# eSAS_BNC_fanout.net
KiCad netlist of a schematic drawn in Altium Designer
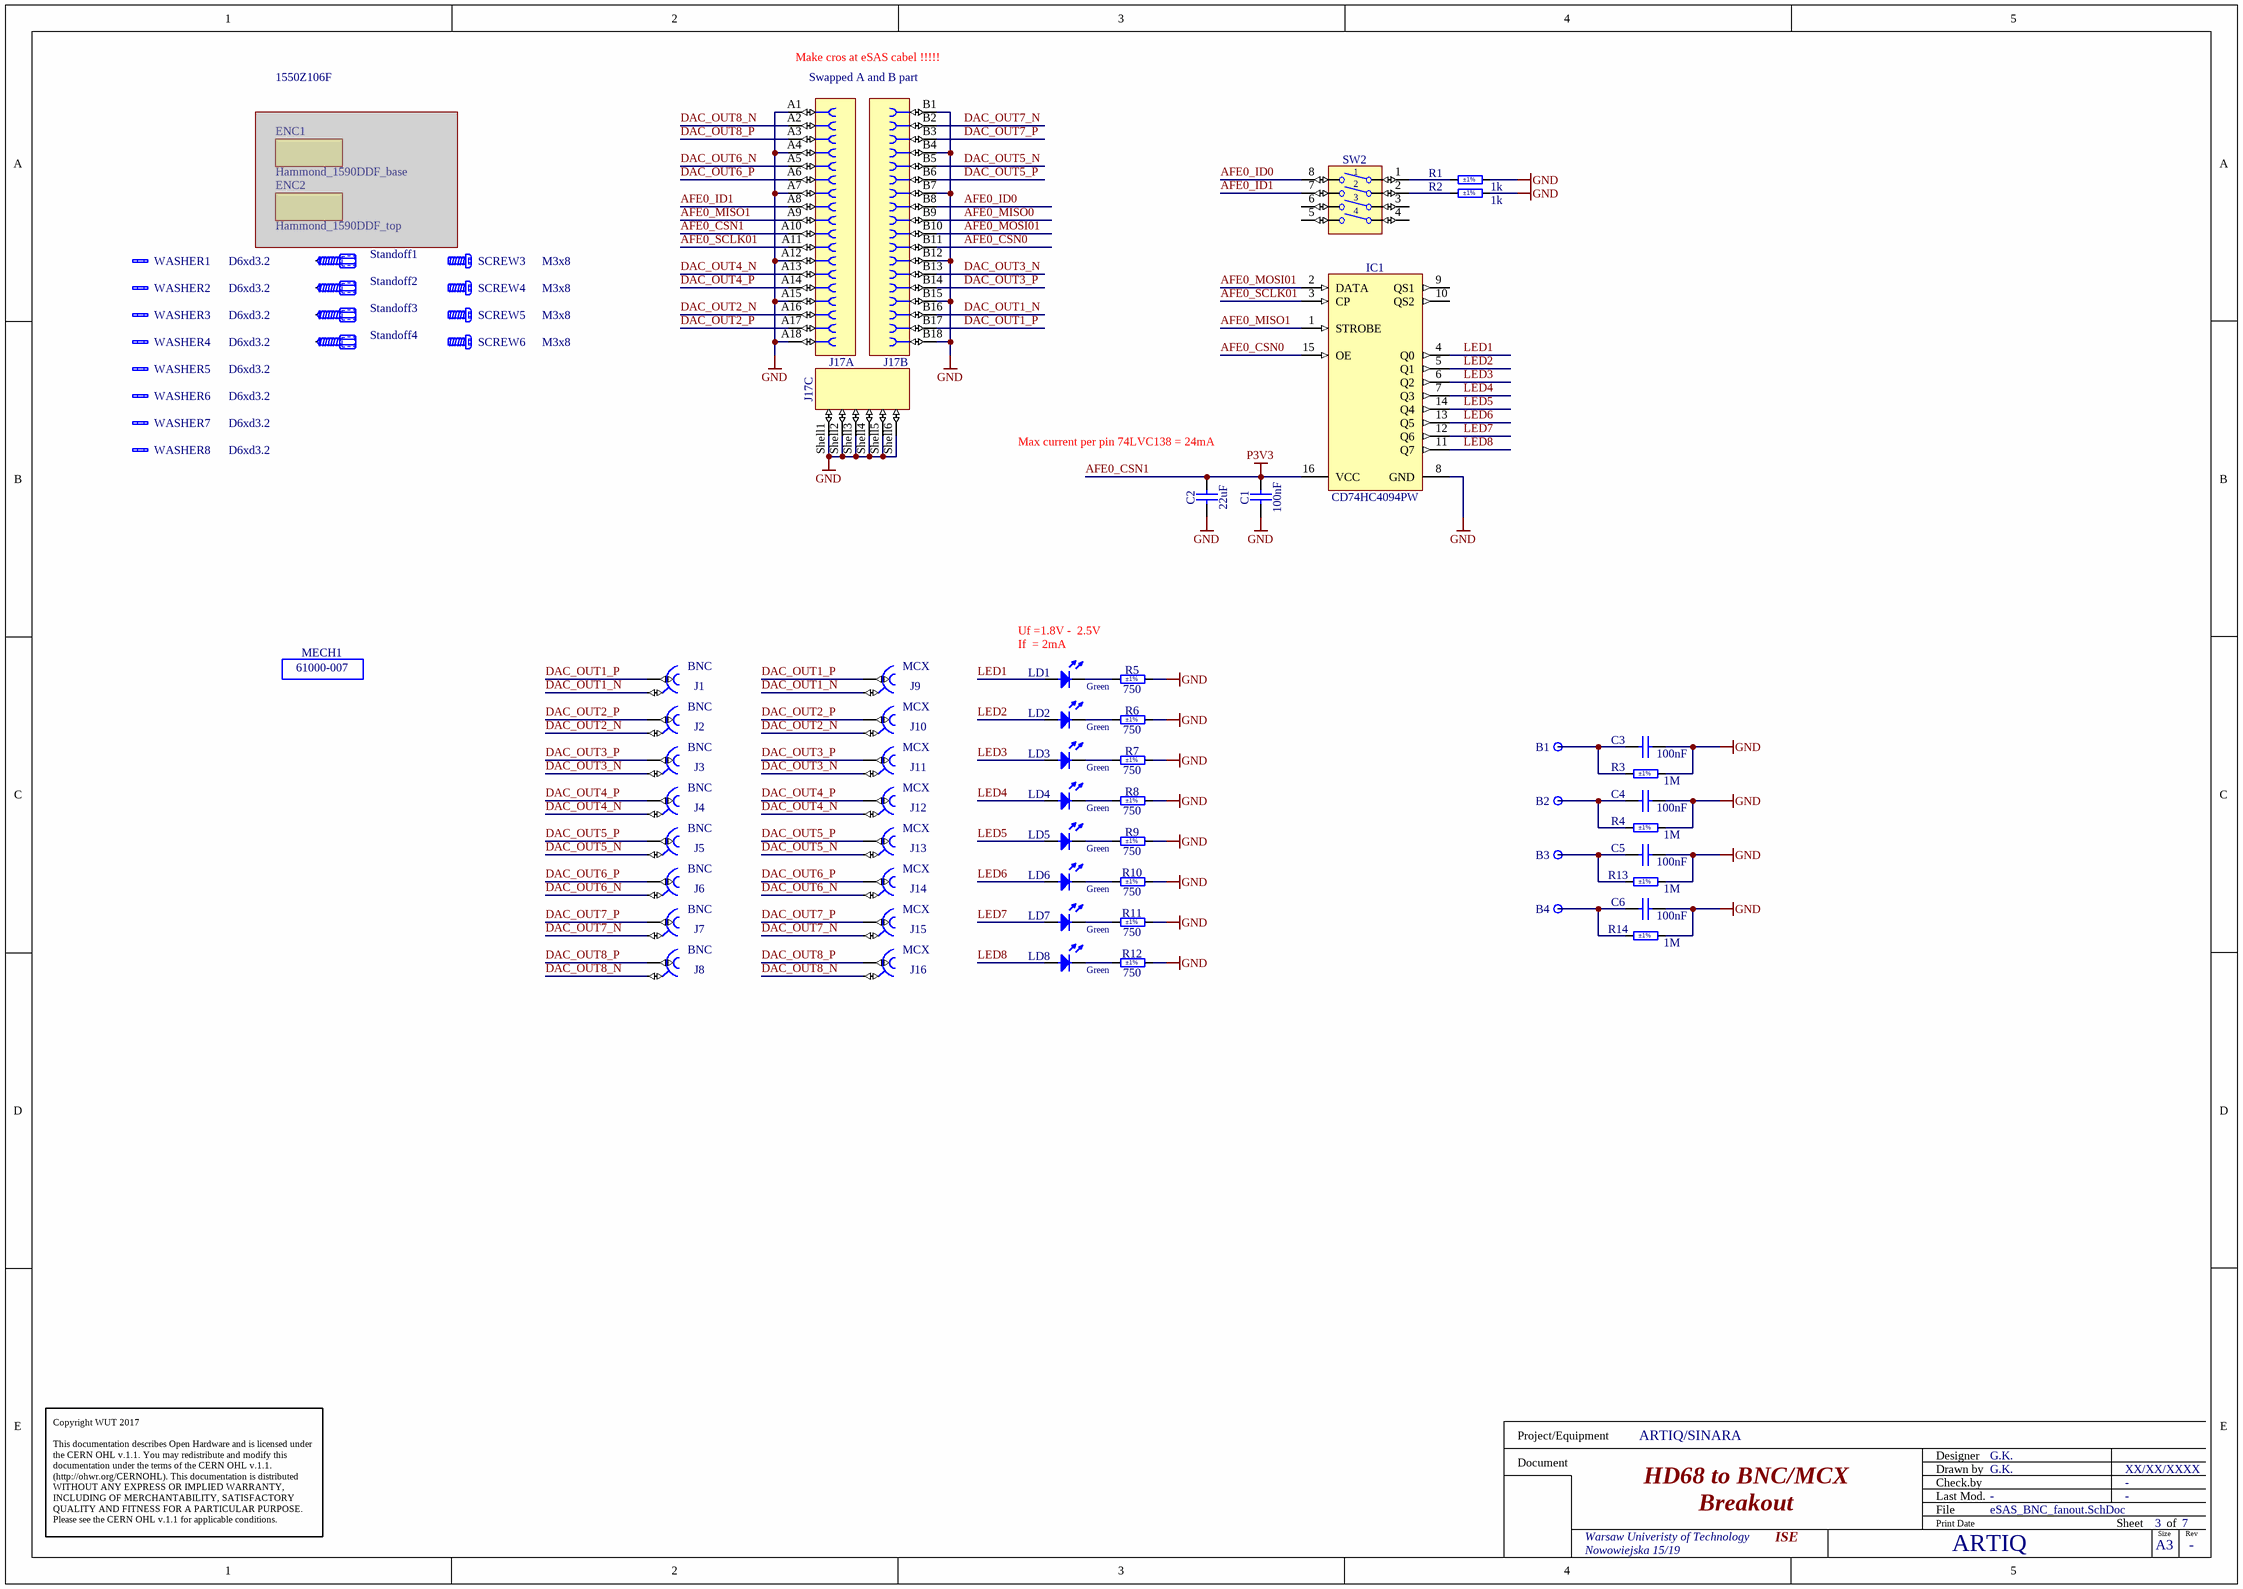
[diagram p0: eSAS_BNC_fanout.SchDoc]

(export (version "E")
  (design (tool "Eeschema 10.0.6"))
  (components
    (comp (ref "B1")
      (value "Plated Hole")
      (footprint "MTG270_500")
      (description "Single Terminal Socket")
      (fields (field (name "PART NUMBER") "PLATED_HOLE2.7_PAD5.0") (field (name "AUTHOR") "CERN DEM JMW"))
      (libsource (lib "Eletro-mechanical") (part "Single Terminal Socket"))
    )
    (comp (ref "B2")
      (value "Plated Hole")
      (footprint "MTG270_500")
      (description "Single Terminal Socket")
      (fields (field (name "PART NUMBER") "PLATED_HOLE2.7_PAD5.0") (field (name "AUTHOR") "CERN DEM JMW"))
      (libsource (lib "Eletro-mechanical") (part "Single Terminal Socket"))
    )
    (comp (ref "B3")
      (value "Plated Hole")
      (footprint "MTG270_500")
      (description "Single Terminal Socket")
      (fields (field (name "PART NUMBER") "PLATED_HOLE2.7_PAD5.0") (field (name "AUTHOR") "CERN DEM JMW"))
      (libsource (lib "Eletro-mechanical") (part "Single Terminal Socket"))
    )
    (comp (ref "B4")
      (value "Plated Hole")
      (footprint "MTG270_500")
      (description "Single Terminal Socket")
      (fields (field (name "PART NUMBER") "PLATED_HOLE2.7_PAD5.0") (field (name "AUTHOR") "CERN DEM JMW"))
      (libsource (lib "Eletro-mechanical") (part "Single Terminal Socket"))
    )
    (comp (ref "C1")
      (value "100nF")
      (footprint "CAPC1608X87N")
      (description "Non-polarised capacitor")
      (fields
        (field (name "PART NUMBER") "CC0603_100NF_50V_10%_X7R")
        (field (name "VOLTAGE") "50V")
        (field (name "AUTHOR") "CERN DEM JLC")
      )
      (libsource (lib "Capacitors") (part "Capacitor - non polarized"))
    )
    (comp (ref "C2")
      (value "22uF")
      (footprint "CAPC1608X90N")
      (description "Non-polarised capacitor")
      (fields
        (field (name "PART NUMBER") "CC0603_22UF_10V_20%_X5R")
        (field (name "VOLTAGE") "10V")
        (field (name "AUTHOR") "CERN DEM BC")
      )
      (libsource (lib "Capacitors") (part "Capacitor - non polarized"))
    )
    (comp (ref "C3")
      (value "100nF")
      (footprint "CAPC1608X90N")
      (description "Non-polarised capacitor")
      (fields
        (field (name "PART NUMBER") "CC0603_100NF_100V_10%_X7R")
        (field (name "VOLTAGE") "100V")
        (field (name "AUTHOR") "CERN DEM JLC")
      )
      (libsource (lib "Capacitors") (part "Capacitor - non polarized"))
    )
    (comp (ref "C4")
      (value "100nF")
      (footprint "CAPC1608X90N")
      (description "Non-polarised capacitor")
      (fields
        (field (name "PART NUMBER") "CC0603_100NF_100V_10%_X7R")
        (field (name "VOLTAGE") "100V")
        (field (name "AUTHOR") "CERN DEM JLC")
      )
      (libsource (lib "Capacitors") (part "Capacitor - non polarized"))
    )
    (comp (ref "C5")
      (value "100nF")
      (footprint "CAPC1608X90N")
      (description "Non-polarised capacitor")
      (fields
        (field (name "PART NUMBER") "CC0603_100NF_100V_10%_X7R")
        (field (name "VOLTAGE") "100V")
        (field (name "AUTHOR") "CERN DEM JLC")
      )
      (libsource (lib "Capacitors") (part "Capacitor - non polarized"))
    )
    (comp (ref "C6")
      (value "100nF")
      (footprint "CAPC1608X90N")
      (description "Non-polarised capacitor")
      (fields
        (field (name "PART NUMBER") "CC0603_100NF_100V_10%_X7R")
        (field (name "VOLTAGE") "100V")
        (field (name "AUTHOR") "CERN DEM JLC")
      )
      (libsource (lib "Capacitors") (part "Capacitor - non polarized"))
    )
    (comp (ref "ENC1")
      (value "Hammond_1590DDF_base")
      (footprint "1590DDF_base")
      (description "Hammond 1590DDF enclosure base part")
      (libsource (lib "Mechanical") (part "Hammond_1590DDF_base"))
    )
    (comp (ref "ENC2")
      (value "Hammond_1590DDF_top")
      (footprint "1590D-DD-E_LID_custom")
      (description "Hammond 1590DDF enclosure lid with custom cutouts")
      (libsource (lib "Mechanical") (part "Hammond_1590DDF_top_custom"))
    )
    (comp (ref "IC1")
      (value "CD74HC4094PW")
      (footprint "SOP65P640X120-16N")
      (description "High−Speed CMOS Logic, 8−Stage Shift and Store Bus Register, Three−State")
      (fields (field (name "MANUFACTURER") "TEXAS INSTRUMENTS") (field (name "AUTHOR") "CERN DEM MR"))
      (libsource (lib "ICs And Semiconductors") (part "744094"))
    )
    (comp (ref "J1")
      (value "BNC")
      (footprint "TYCO_5-1634506-1")
      (fields
        (field (name "PART NUMBER") "TYCO_5-1634506-1")
        (field (name "MANUFACTURER") "TYCO ELECTRONICS")
        (field (name "MANUFACTURER PART NUMBER") "5-1634506-1")
        (field (name "AUTHOR") "CERN DEM JLC")
      )
      (libsource (lib "Connectors") (part "Coax_1Female_1Shield"))
    )
    (comp (ref "J2")
      (value "BNC")
      (footprint "TYCO_5-1634506-1")
      (fields
        (field (name "PART NUMBER") "TYCO_5-1634506-1")
        (field (name "MANUFACTURER") "TYCO ELECTRONICS")
        (field (name "MANUFACTURER PART NUMBER") "5-1634506-1")
        (field (name "AUTHOR") "CERN DEM JLC")
      )
      (libsource (lib "Connectors") (part "Coax_1Female_1Shield"))
    )
    (comp (ref "J3")
      (value "BNC")
      (footprint "TYCO_5-1634506-1")
      (fields
        (field (name "PART NUMBER") "TYCO_5-1634506-1")
        (field (name "MANUFACTURER") "TYCO ELECTRONICS")
        (field (name "MANUFACTURER PART NUMBER") "5-1634506-1")
        (field (name "AUTHOR") "CERN DEM JLC")
      )
      (libsource (lib "Connectors") (part "Coax_1Female_1Shield"))
    )
    (comp (ref "J4")
      (value "BNC")
      (footprint "TYCO_5-1634506-1")
      (fields
        (field (name "PART NUMBER") "TYCO_5-1634506-1")
        (field (name "MANUFACTURER") "TYCO ELECTRONICS")
        (field (name "MANUFACTURER PART NUMBER") "5-1634506-1")
        (field (name "AUTHOR") "CERN DEM JLC")
      )
      (libsource (lib "Connectors") (part "Coax_1Female_1Shield"))
    )
    (comp (ref "J5")
      (value "BNC")
      (footprint "TYCO_5-1634506-1")
      (fields
        (field (name "PART NUMBER") "TYCO_5-1634506-1")
        (field (name "MANUFACTURER") "TYCO ELECTRONICS")
        (field (name "MANUFACTURER PART NUMBER") "5-1634506-1")
        (field (name "AUTHOR") "CERN DEM JLC")
      )
      (libsource (lib "Connectors") (part "Coax_1Female_1Shield"))
    )
    (comp (ref "J6")
      (value "BNC")
      (footprint "TYCO_5-1634506-1")
      (fields
        (field (name "PART NUMBER") "TYCO_5-1634506-1")
        (field (name "MANUFACTURER") "TYCO ELECTRONICS")
        (field (name "MANUFACTURER PART NUMBER") "5-1634506-1")
        (field (name "AUTHOR") "CERN DEM JLC")
      )
      (libsource (lib "Connectors") (part "Coax_1Female_1Shield"))
    )
    (comp (ref "J7")
      (value "BNC")
      (footprint "TYCO_5-1634506-1")
      (fields
        (field (name "PART NUMBER") "TYCO_5-1634506-1")
        (field (name "MANUFACTURER") "TYCO ELECTRONICS")
        (field (name "MANUFACTURER PART NUMBER") "5-1634506-1")
        (field (name "AUTHOR") "CERN DEM JLC")
      )
      (libsource (lib "Connectors") (part "Coax_1Female_1Shield"))
    )
    (comp (ref "J8")
      (value "BNC")
      (footprint "TYCO_5-1634506-1")
      (fields
        (field (name "PART NUMBER") "TYCO_5-1634506-1")
        (field (name "MANUFACTURER") "TYCO ELECTRONICS")
        (field (name "MANUFACTURER PART NUMBER") "5-1634506-1")
        (field (name "AUTHOR") "CERN DEM JLC")
      )
      (libsource (lib "Connectors") (part "Coax_1Female_1Shield"))
    )
    (comp (ref "J9")
      (value "MCX")
      (footprint "AMPHENOL_919-109J-51PX")
      (fields
        (field (name "PART NUMBER") "AMPHENOL_919-109J-51PX")
        (field (name "MANUFACTURER") "AMPHENOL")
        (field (name "MANUFACTURER PART NUMBER") "919-109J-51PX (MCX6251B1-3GT30G-50)")
        (field (name "AUTHOR") "CERN DEM BC")
      )
      (libsource (lib "Connectors") (part "Coax_1Female_1Shield"))
    )
    (comp (ref "J10")
      (value "MCX")
      (footprint "AMPHENOL_919-109J-51PX")
      (fields
        (field (name "PART NUMBER") "AMPHENOL_919-109J-51PX")
        (field (name "MANUFACTURER") "AMPHENOL")
        (field (name "MANUFACTURER PART NUMBER") "919-109J-51PX (MCX6251B1-3GT30G-50)")
        (field (name "AUTHOR") "CERN DEM BC")
      )
      (libsource (lib "Connectors") (part "Coax_1Female_1Shield"))
    )
    (comp (ref "J11")
      (value "MCX")
      (footprint "AMPHENOL_919-109J-51PX")
      (fields
        (field (name "PART NUMBER") "AMPHENOL_919-109J-51PX")
        (field (name "MANUFACTURER") "AMPHENOL")
        (field (name "MANUFACTURER PART NUMBER") "919-109J-51PX (MCX6251B1-3GT30G-50)")
        (field (name "AUTHOR") "CERN DEM BC")
      )
      (libsource (lib "Connectors") (part "Coax_1Female_1Shield"))
    )
    (comp (ref "J12")
      (value "MCX")
      (footprint "AMPHENOL_919-109J-51PX")
      (fields
        (field (name "PART NUMBER") "AMPHENOL_919-109J-51PX")
        (field (name "MANUFACTURER") "AMPHENOL")
        (field (name "MANUFACTURER PART NUMBER") "919-109J-51PX (MCX6251B1-3GT30G-50)")
        (field (name "AUTHOR") "CERN DEM BC")
      )
      (libsource (lib "Connectors") (part "Coax_1Female_1Shield"))
    )
    (comp (ref "J13")
      (value "MCX")
      (footprint "AMPHENOL_919-109J-51PX")
      (fields
        (field (name "PART NUMBER") "AMPHENOL_919-109J-51PX")
        (field (name "MANUFACTURER") "AMPHENOL")
        (field (name "MANUFACTURER PART NUMBER") "919-109J-51PX (MCX6251B1-3GT30G-50)")
        (field (name "AUTHOR") "CERN DEM BC")
      )
      (libsource (lib "Connectors") (part "Coax_1Female_1Shield"))
    )
    (comp (ref "J14")
      (value "MCX")
      (footprint "AMPHENOL_919-109J-51PX")
      (fields
        (field (name "PART NUMBER") "AMPHENOL_919-109J-51PX")
        (field (name "MANUFACTURER") "AMPHENOL")
        (field (name "MANUFACTURER PART NUMBER") "919-109J-51PX (MCX6251B1-3GT30G-50)")
        (field (name "AUTHOR") "CERN DEM BC")
      )
      (libsource (lib "Connectors") (part "Coax_1Female_1Shield"))
    )
    (comp (ref "J15")
      (value "MCX")
      (footprint "AMPHENOL_919-109J-51PX")
      (fields
        (field (name "PART NUMBER") "AMPHENOL_919-109J-51PX")
        (field (name "MANUFACTURER") "AMPHENOL")
        (field (name "MANUFACTURER PART NUMBER") "919-109J-51PX (MCX6251B1-3GT30G-50)")
        (field (name "AUTHOR") "CERN DEM BC")
      )
      (libsource (lib "Connectors") (part "Coax_1Female_1Shield"))
    )
    (comp (ref "J16")
      (value "MCX")
      (footprint "AMPHENOL_919-109J-51PX")
      (fields
        (field (name "PART NUMBER") "AMPHENOL_919-109J-51PX")
        (field (name "MANUFACTURER") "AMPHENOL")
        (field (name "MANUFACTURER PART NUMBER") "919-109J-51PX (MCX6251B1-3GT30G-50)")
        (field (name "AUTHOR") "CERN DEM BC")
      )
      (libsource (lib "Connectors") (part "Coax_1Female_1Shield"))
    )
    (comp (ref "J17")
      (value "iPass™")
      (footprint "MOLEX_75783-0107")
      (fields
        (field (name "PART NUMBER") "MOLEX 75783-0107 / 75783-0136")
        (field (name "MANUFACTURER") "MOLEX")
        (field (name "MANUFACTURER PART NUMBER") "75783-0107 / 75783-0136")
        (field (name "AUTHOR") "CERN DEM JLC")
      )
      (libsource (lib "") (part "MOLEX_75783-0107_2"))
    )
    (comp (ref "LD1")
      (value "Green")
      (footprint "LED_KINGBRIGHT_KP-1608CGCK")
      (description "LED Green 1C 2A")
      (fields
        (field (name "PART NUMBER") "LED_KINGBRIGHT_KP-1608CGCK")
        (field (name "MANUFACTURER") "KINGBRIGHT")
        (field (name "AUTHOR") "CERN DEM HF")
      )
      (libsource (lib "ICs And Semiconductors") (part "LED Green 1C 2A"))
    )
    (comp (ref "LD2")
      (value "Green")
      (footprint "LED_KINGBRIGHT_KP-1608CGCK")
      (description "LED Green 1C 2A")
      (fields
        (field (name "PART NUMBER") "LED_KINGBRIGHT_KP-1608CGCK")
        (field (name "MANUFACTURER") "KINGBRIGHT")
        (field (name "AUTHOR") "CERN DEM HF")
      )
      (libsource (lib "ICs And Semiconductors") (part "LED Green 1C 2A"))
    )
    (comp (ref "LD3")
      (value "Green")
      (footprint "LED_KINGBRIGHT_KP-1608CGCK")
      (description "LED Green 1C 2A")
      (fields
        (field (name "PART NUMBER") "LED_KINGBRIGHT_KP-1608CGCK")
        (field (name "MANUFACTURER") "KINGBRIGHT")
        (field (name "AUTHOR") "CERN DEM HF")
      )
      (libsource (lib "ICs And Semiconductors") (part "LED Green 1C 2A"))
    )
    (comp (ref "LD4")
      (value "Green")
      (footprint "LED_KINGBRIGHT_KP-1608CGCK")
      (description "LED Green 1C 2A")
      (fields
        (field (name "PART NUMBER") "LED_KINGBRIGHT_KP-1608CGCK")
        (field (name "MANUFACTURER") "KINGBRIGHT")
        (field (name "AUTHOR") "CERN DEM HF")
      )
      (libsource (lib "ICs And Semiconductors") (part "LED Green 1C 2A"))
    )
    (comp (ref "LD5")
      (value "Green")
      (footprint "LED_KINGBRIGHT_KP-1608CGCK")
      (description "LED Green 1C 2A")
      (fields
        (field (name "PART NUMBER") "LED_KINGBRIGHT_KP-1608CGCK")
        (field (name "MANUFACTURER") "KINGBRIGHT")
        (field (name "AUTHOR") "CERN DEM HF")
      )
      (libsource (lib "ICs And Semiconductors") (part "LED Green 1C 2A"))
    )
    (comp (ref "LD6")
      (value "Green")
      (footprint "LED_KINGBRIGHT_KP-1608CGCK")
      (description "LED Green 1C 2A")
      (fields
        (field (name "PART NUMBER") "LED_KINGBRIGHT_KP-1608CGCK")
        (field (name "MANUFACTURER") "KINGBRIGHT")
        (field (name "AUTHOR") "CERN DEM HF")
      )
      (libsource (lib "ICs And Semiconductors") (part "LED Green 1C 2A"))
    )
    (comp (ref "LD7")
      (value "Green")
      (footprint "LED_KINGBRIGHT_KP-1608CGCK")
      (description "LED Green 1C 2A")
      (fields
        (field (name "PART NUMBER") "LED_KINGBRIGHT_KP-1608CGCK")
        (field (name "MANUFACTURER") "KINGBRIGHT")
        (field (name "AUTHOR") "CERN DEM HF")
      )
      (libsource (lib "ICs And Semiconductors") (part "LED Green 1C 2A"))
    )
    (comp (ref "LD8")
      (value "Green")
      (footprint "LED_KINGBRIGHT_KP-1608CGCK")
      (description "LED Green 1C 2A")
      (fields
        (field (name "PART NUMBER") "LED_KINGBRIGHT_KP-1608CGCK")
        (field (name "MANUFACTURER") "KINGBRIGHT")
        (field (name "AUTHOR") "CERN DEM HF")
      )
      (libsource (lib "ICs And Semiconductors") (part "LED Green 1C 2A"))
    )
    (comp (ref "MECH1")
      (value "61000-007")
      (footprint "GENERIC_MECH")
      (description "PCB Solder Side Cover, 3 U, 100 mm x 160 mm, 55°C Schroff insulating plate")
      (fields (field (name "MANUFACTURER") "Schroff") (field (name "AUTHOR") "GK"))
      (libsource (lib "Mechanical") (part "Generic_mechanical"))
    )
    (comp (ref "R1")
      (value "1k")
      (footprint "RESC1608X55N")
      (description "Resistor - 1%")
      (fields
        (field (name "TOLERANCE") "±1%")
        (field (name "PART NUMBER") "R0603_1K_1%_0.1W_100PPM")
        (field (name "POWER") "0.1W")
        (field (name "AUTHOR") "CERN DEM JLC")
      )
      (libsource (lib "Resistors") (part "Resistor - 1%"))
    )
    (comp (ref "R2")
      (value "1k")
      (footprint "RESC1608X55N")
      (description "Resistor - 1%")
      (fields
        (field (name "TOLERANCE") "±1%")
        (field (name "PART NUMBER") "R0603_1K_1%_0.1W_100PPM")
        (field (name "POWER") "0.1W")
        (field (name "AUTHOR") "CERN DEM JLC")
      )
      (libsource (lib "Resistors") (part "Resistor - 1%"))
    )
    (comp (ref "R3")
      (value "1M")
      (footprint "RESC1608X55N")
      (description "Resistor - 1%")
      (fields
        (field (name "TOLERANCE") "±1%")
        (field (name "PART NUMBER") "R0603_1M_1%_0.1W_100PPM")
        (field (name "POWER") "0.1W")
        (field (name "AUTHOR") "CERN DEM JLC")
      )
      (libsource (lib "Resistors") (part "Resistor - 1%"))
    )
    (comp (ref "R4")
      (value "1M")
      (footprint "RESC1608X55N")
      (description "Resistor - 1%")
      (fields
        (field (name "TOLERANCE") "±1%")
        (field (name "PART NUMBER") "R0603_1M_1%_0.1W_100PPM")
        (field (name "POWER") "0.1W")
        (field (name "AUTHOR") "CERN DEM JLC")
      )
      (libsource (lib "Resistors") (part "Resistor - 1%"))
    )
    (comp (ref "R5")
      (value "750")
      (footprint "RESC1608X55N")
      (description "Resistor - 1%")
      (fields
        (field (name "TOLERANCE") "±1%")
        (field (name "PART NUMBER") "R0603_750R_1%_0.1W_100PPM")
        (field (name "POWER") "0.1W")
        (field (name "AUTHOR") "CERN DEM JLC")
      )
      (libsource (lib "Resistors") (part "Resistor - 1%"))
    )
    (comp (ref "R6")
      (value "750")
      (footprint "RESC1608X55N")
      (description "Resistor - 1%")
      (fields
        (field (name "TOLERANCE") "±1%")
        (field (name "PART NUMBER") "R0603_750R_1%_0.1W_100PPM")
        (field (name "POWER") "0.1W")
        (field (name "AUTHOR") "CERN DEM JLC")
      )
      (libsource (lib "Resistors") (part "Resistor - 1%"))
    )
    (comp (ref "R7")
      (value "750")
      (footprint "RESC1608X55N")
      (description "Resistor - 1%")
      (fields
        (field (name "TOLERANCE") "±1%")
        (field (name "PART NUMBER") "R0603_750R_1%_0.1W_100PPM")
        (field (name "POWER") "0.1W")
        (field (name "AUTHOR") "CERN DEM JLC")
      )
      (libsource (lib "Resistors") (part "Resistor - 1%"))
    )
    (comp (ref "R8")
      (value "750")
      (footprint "RESC1608X55N")
      (description "Resistor - 1%")
      (fields
        (field (name "TOLERANCE") "±1%")
        (field (name "PART NUMBER") "R0603_750R_1%_0.1W_100PPM")
        (field (name "POWER") "0.1W")
        (field (name "AUTHOR") "CERN DEM JLC")
      )
      (libsource (lib "Resistors") (part "Resistor - 1%"))
    )
    (comp (ref "R9")
      (value "750")
      (footprint "RESC1608X55N")
      (description "Resistor - 1%")
      (fields
        (field (name "TOLERANCE") "±1%")
        (field (name "PART NUMBER") "R0603_750R_1%_0.1W_100PPM")
        (field (name "POWER") "0.1W")
        (field (name "AUTHOR") "CERN DEM JLC")
      )
      (libsource (lib "Resistors") (part "Resistor - 1%"))
    )
    (comp (ref "R10")
      (value "750")
      (footprint "RESC1608X55N")
      (description "Resistor - 1%")
      (fields
        (field (name "TOLERANCE") "±1%")
        (field (name "PART NUMBER") "R0603_750R_1%_0.1W_100PPM")
        (field (name "POWER") "0.1W")
        (field (name "AUTHOR") "CERN DEM JLC")
      )
      (libsource (lib "Resistors") (part "Resistor - 1%"))
    )
    (comp (ref "R11")
      (value "750")
      (footprint "RESC1608X55N")
      (description "Resistor - 1%")
      (fields
        (field (name "TOLERANCE") "±1%")
        (field (name "PART NUMBER") "R0603_750R_1%_0.1W_100PPM")
        (field (name "POWER") "0.1W")
        (field (name "AUTHOR") "CERN DEM JLC")
      )
      (libsource (lib "Resistors") (part "Resistor - 1%"))
    )
    (comp (ref "R12")
      (value "750")
      (footprint "RESC1608X55N")
      (description "Resistor - 1%")
      (fields
        (field (name "TOLERANCE") "±1%")
        (field (name "PART NUMBER") "R0603_750R_1%_0.1W_100PPM")
        (field (name "POWER") "0.1W")
        (field (name "AUTHOR") "CERN DEM JLC")
      )
      (libsource (lib "Resistors") (part "Resistor - 1%"))
    )
    (comp (ref "R13")
      (value "1M")
      (footprint "RESC1608X55N")
      (description "Resistor - 1%")
      (fields
        (field (name "TOLERANCE") "±1%")
        (field (name "PART NUMBER") "R0603_1M_1%_0.1W_100PPM")
        (field (name "POWER") "0.1W")
        (field (name "AUTHOR") "CERN DEM JLC")
      )
      (libsource (lib "Resistors") (part "Resistor - 1%"))
    )
    (comp (ref "R14")
      (value "1M")
      (footprint "RESC1608X55N")
      (description "Resistor - 1%")
      (fields
        (field (name "TOLERANCE") "±1%")
        (field (name "PART NUMBER") "R0603_1M_1%_0.1W_100PPM")
        (field (name "POWER") "0.1W")
        (field (name "AUTHOR") "CERN DEM JLC")
      )
      (libsource (lib "Resistors") (part "Resistor - 1%"))
    )
    (comp (ref "SCREW3")
      (value "M3x8")
      (footprint "BOSSARD_BN5687-3061606_h")
      (description "Screw")
      (fields
        (field (name "PART NUMBER") "BOSSARD_BN5687-3061606_h")
        (field (name "MANUFACTURER") "BOSSARD")
        (field (name "AUTHOR") "CERN DEM JLC")
      )
      (libsource (lib "Eletro-mechanical") (part "Screw"))
    )
    (comp (ref "SCREW4")
      (value "M3x8")
      (footprint "BOSSARD_BN5687-3061606_h")
      (description "Screw")
      (fields
        (field (name "PART NUMBER") "BOSSARD_BN5687-3061606_h")
        (field (name "MANUFACTURER") "BOSSARD")
        (field (name "AUTHOR") "CERN DEM JLC")
      )
      (libsource (lib "Eletro-mechanical") (part "Screw"))
    )
    (comp (ref "SCREW5")
      (value "M3x8")
      (footprint "BOSSARD_BN5687-3061606_h")
      (description "Screw")
      (fields
        (field (name "PART NUMBER") "BOSSARD_BN5687-3061606_h")
        (field (name "MANUFACTURER") "BOSSARD")
        (field (name "AUTHOR") "CERN DEM JLC")
      )
      (libsource (lib "Eletro-mechanical") (part "Screw"))
    )
    (comp (ref "SCREW6")
      (value "M3x8")
      (footprint "BOSSARD_BN5687-3061606_h")
      (description "Screw")
      (fields
        (field (name "PART NUMBER") "BOSSARD_BN5687-3061606_h")
        (field (name "MANUFACTURER") "BOSSARD")
        (field (name "AUTHOR") "CERN DEM JLC")
      )
      (libsource (lib "Eletro-mechanical") (part "Screw"))
    )
    (comp (ref "Standoff1")
      (value "~")
      (footprint "ETTINGER_005.13.103")
      (description "Standoff Male-Female")
      (fields
        (field (name "PART NUMBER") "ETTINGER_005.13.103")
        (field (name "MANUFACTURER") "ETTINGER")
        (field (name "AUTHOR") "CERN DEM HF")
      )
      (libsource (lib "Eletro-mechanical") (part "Standoff Male-Female"))
    )
    (comp (ref "Standoff2")
      (value "~")
      (footprint "ETTINGER_005.13.103")
      (description "Standoff Male-Female")
      (fields
        (field (name "PART NUMBER") "ETTINGER_005.13.103")
        (field (name "MANUFACTURER") "ETTINGER")
        (field (name "AUTHOR") "CERN DEM HF")
      )
      (libsource (lib "Eletro-mechanical") (part "Standoff Male-Female"))
    )
    (comp (ref "Standoff3")
      (value "~")
      (footprint "ETTINGER_005.13.103")
      (description "Standoff Male-Female")
      (fields
        (field (name "PART NUMBER") "ETTINGER_005.13.103")
        (field (name "MANUFACTURER") "ETTINGER")
        (field (name "AUTHOR") "CERN DEM HF")
      )
      (libsource (lib "Eletro-mechanical") (part "Standoff Male-Female"))
    )
    (comp (ref "Standoff4")
      (value "~")
      (footprint "ETTINGER_005.13.103")
      (description "Standoff Male-Female")
      (fields
        (field (name "PART NUMBER") "ETTINGER_005.13.103")
        (field (name "MANUFACTURER") "ETTINGER")
        (field (name "AUTHOR") "CERN DEM HF")
      )
      (libsource (lib "Eletro-mechanical") (part "Standoff Male-Female"))
    )
    (comp (ref "SW2")
      (value "Switch")
      (footprint "SW_OMRON_A6DR-4100")
      (description "4 Ways SPST DIP Switch")
      (fields
        (field (name "PART NUMBER") "SW_OMRON_A6DR-4100")
        (field (name "MANUFACTURER") "OMRON")
        (field (name "AUTHOR") "CERN DEM JLC")
      )
      (libsource (lib "Eletro-mechanical") (part "SW 4x SPST DIP Switch"))
    )
    (comp (ref "WASHER1")
      (value "D6xd3.2")
      (footprint "BOSSARD_BN83728-8243964_v")
      (description "Washer")
      (fields
        (field (name "PART NUMBER") "BOSSARD_BN83728-8243964_v")
        (field (name "MANUFACTURER") "BOSSARD")
        (field (name "AUTHOR") "CERN DEM JLC")
      )
      (libsource (lib "Eletro-mechanical") (part "Washer"))
    )
    (comp (ref "WASHER2")
      (value "D6xd3.2")
      (footprint "BOSSARD_BN83728-8243964_v")
      (description "Washer")
      (fields
        (field (name "PART NUMBER") "BOSSARD_BN83728-8243964_v")
        (field (name "MANUFACTURER") "BOSSARD")
        (field (name "AUTHOR") "CERN DEM JLC")
      )
      (libsource (lib "Eletro-mechanical") (part "Washer"))
    )
    (comp (ref "WASHER3")
      (value "D6xd3.2")
      (footprint "BOSSARD_BN83728-8243964_v")
      (description "Washer")
      (fields
        (field (name "PART NUMBER") "BOSSARD_BN83728-8243964_v")
        (field (name "MANUFACTURER") "BOSSARD")
        (field (name "AUTHOR") "CERN DEM JLC")
      )
      (libsource (lib "Eletro-mechanical") (part "Washer"))
    )
    (comp (ref "WASHER4")
      (value "D6xd3.2")
      (footprint "BOSSARD_BN83728-8243964_v")
      (description "Washer")
      (fields
        (field (name "PART NUMBER") "BOSSARD_BN83728-8243964_v")
        (field (name "MANUFACTURER") "BOSSARD")
        (field (name "AUTHOR") "CERN DEM JLC")
      )
      (libsource (lib "Eletro-mechanical") (part "Washer"))
    )
    (comp (ref "WASHER5")
      (value "D6xd3.2")
      (footprint "BOSSARD_BN83728-8243964_v")
      (description "Washer")
      (fields
        (field (name "PART NUMBER") "BOSSARD_BN83728-8243964_v")
        (field (name "MANUFACTURER") "BOSSARD")
        (field (name "AUTHOR") "CERN DEM JLC")
      )
      (libsource (lib "Eletro-mechanical") (part "Washer"))
    )
    (comp (ref "WASHER6")
      (value "D6xd3.2")
      (footprint "BOSSARD_BN83728-8243964_v")
      (description "Washer")
      (fields
        (field (name "PART NUMBER") "BOSSARD_BN83728-8243964_v")
        (field (name "MANUFACTURER") "BOSSARD")
        (field (name "AUTHOR") "CERN DEM JLC")
      )
      (libsource (lib "Eletro-mechanical") (part "Washer"))
    )
    (comp (ref "WASHER7")
      (value "D6xd3.2")
      (footprint "BOSSARD_BN83728-8243964_v")
      (description "Washer")
      (fields
        (field (name "PART NUMBER") "BOSSARD_BN83728-8243964_v")
        (field (name "MANUFACTURER") "BOSSARD")
        (field (name "AUTHOR") "CERN DEM JLC")
      )
      (libsource (lib "Eletro-mechanical") (part "Washer"))
    )
    (comp (ref "WASHER8")
      (value "D6xd3.2")
      (footprint "BOSSARD_BN83728-8243964_v")
      (description "Washer")
      (fields
        (field (name "PART NUMBER") "BOSSARD_BN83728-8243964_v")
        (field (name "MANUFACTURER") "BOSSARD")
        (field (name "AUTHOR") "CERN DEM JLC")
      )
      (libsource (lib "Eletro-mechanical") (part "Washer"))
    )
  )
  (nets
    (net (code "1") (name "/AFE0_CSN0") (class "Default")
      (node (ref "IC1") (pin "15") (pinfunction "OE_15") (pintype "input"))
      (node (ref "J17") (pin "B11") (pinfunction "B11_B11") (pintype "bidirectional"))
    )
    (net (code "2") (name "/AFE0_ID0") (class "Default")
      (node (ref "J17") (pin "B8") (pinfunction "B8_B8") (pintype "bidirectional"))
      (node (ref "SW2") (pin "8") (pinfunction "8_8") (pintype "bidirectional"))
    )
    (net (code "3") (name "/AFE0_ID1") (class "Default")
      (node (ref "J17") (pin "A8") (pinfunction "A8_A8") (pintype "bidirectional"))
      (node (ref "SW2") (pin "7") (pinfunction "7_7") (pintype "bidirectional"))
    )
    (net (code "4") (name "/AFE0_MISO0") (class "Default")
      (node (ref "J17") (pin "B9") (pinfunction "B9_B9") (pintype "bidirectional"))
    )
    (net (code "5") (name "/AFE0_MISO1") (class "Default")
      (node (ref "IC1") (pin "1") (pinfunction "STROBE_1") (pintype "input"))
      (node (ref "J17") (pin "A9") (pinfunction "A9_A9") (pintype "bidirectional"))
    )
    (net (code "6") (name "/AFE0_MOSI01") (class "Default")
      (node (ref "IC1") (pin "2") (pinfunction "DATA_2") (pintype "input"))
      (node (ref "J17") (pin "B10") (pinfunction "B10_B10") (pintype "bidirectional"))
    )
    (net (code "7") (name "/AFE0_SCLK01") (class "Default")
      (node (ref "IC1") (pin "3") (pinfunction "CP_3") (pintype "input"))
      (node (ref "J17") (pin "A11") (pinfunction "A11_A11") (pintype "bidirectional"))
    )
    (net (code "8") (name "/DAC_OUT1_N") (class "Default")
      (node (ref "J1") (pin "2") (pinfunction "2_2") (pintype "bidirectional"))
      (node (ref "J17") (pin "B16") (pinfunction "B16_B16") (pintype "bidirectional"))
      (node (ref "J9") (pin "2") (pinfunction "2_2") (pintype "bidirectional"))
    )
    (net (code "9") (name "/DAC_OUT1_P") (class "Default")
      (node (ref "J1") (pin "1") (pinfunction "1_1") (pintype "bidirectional"))
      (node (ref "J17") (pin "B17") (pinfunction "B17_B17") (pintype "bidirectional"))
      (node (ref "J9") (pin "1") (pinfunction "1_1") (pintype "bidirectional"))
    )
    (net (code "10") (name "/DAC_OUT2_N") (class "Default")
      (node (ref "J10") (pin "2") (pinfunction "2_2") (pintype "bidirectional"))
      (node (ref "J17") (pin "A16") (pinfunction "A16_A16") (pintype "bidirectional"))
      (node (ref "J2") (pin "2") (pinfunction "2_2") (pintype "bidirectional"))
    )
    (net (code "11") (name "/DAC_OUT2_P") (class "Default")
      (node (ref "J10") (pin "1") (pinfunction "1_1") (pintype "bidirectional"))
      (node (ref "J17") (pin "A17") (pinfunction "A17_A17") (pintype "bidirectional"))
      (node (ref "J2") (pin "1") (pinfunction "1_1") (pintype "bidirectional"))
    )
    (net (code "12") (name "/DAC_OUT3_N") (class "Default")
      (node (ref "J11") (pin "2") (pinfunction "2_2") (pintype "bidirectional"))
      (node (ref "J17") (pin "B13") (pinfunction "B13_B13") (pintype "bidirectional"))
      (node (ref "J3") (pin "2") (pinfunction "2_2") (pintype "bidirectional"))
    )
    (net (code "13") (name "/DAC_OUT3_P") (class "Default")
      (node (ref "J11") (pin "1") (pinfunction "1_1") (pintype "bidirectional"))
      (node (ref "J17") (pin "B14") (pinfunction "B14_B14") (pintype "bidirectional"))
      (node (ref "J3") (pin "1") (pinfunction "1_1") (pintype "bidirectional"))
    )
    (net (code "14") (name "/DAC_OUT4_N") (class "Default")
      (node (ref "J12") (pin "2") (pinfunction "2_2") (pintype "bidirectional"))
      (node (ref "J17") (pin "A13") (pinfunction "A13_A13") (pintype "bidirectional"))
      (node (ref "J4") (pin "2") (pinfunction "2_2") (pintype "bidirectional"))
    )
    (net (code "15") (name "/DAC_OUT4_P") (class "Default")
      (node (ref "J12") (pin "1") (pinfunction "1_1") (pintype "bidirectional"))
      (node (ref "J17") (pin "A14") (pinfunction "A14_A14") (pintype "bidirectional"))
      (node (ref "J4") (pin "1") (pinfunction "1_1") (pintype "bidirectional"))
    )
    (net (code "16") (name "/DAC_OUT5_N") (class "Default")
      (node (ref "J13") (pin "2") (pinfunction "2_2") (pintype "bidirectional"))
      (node (ref "J17") (pin "B5") (pinfunction "B5_B5") (pintype "bidirectional"))
      (node (ref "J5") (pin "2") (pinfunction "2_2") (pintype "bidirectional"))
    )
    (net (code "17") (name "/DAC_OUT5_P") (class "Default")
      (node (ref "J13") (pin "1") (pinfunction "1_1") (pintype "bidirectional"))
      (node (ref "J17") (pin "B6") (pinfunction "B6_B6") (pintype "bidirectional"))
      (node (ref "J5") (pin "1") (pinfunction "1_1") (pintype "bidirectional"))
    )
    (net (code "18") (name "/DAC_OUT6_N") (class "Default")
      (node (ref "J14") (pin "2") (pinfunction "2_2") (pintype "bidirectional"))
      (node (ref "J17") (pin "A5") (pinfunction "A5_A5") (pintype "bidirectional"))
      (node (ref "J6") (pin "2") (pinfunction "2_2") (pintype "bidirectional"))
    )
    (net (code "19") (name "/DAC_OUT6_P") (class "Default")
      (node (ref "J14") (pin "1") (pinfunction "1_1") (pintype "bidirectional"))
      (node (ref "J17") (pin "A6") (pinfunction "A6_A6") (pintype "bidirectional"))
      (node (ref "J6") (pin "1") (pinfunction "1_1") (pintype "bidirectional"))
    )
    (net (code "20") (name "/DAC_OUT7_N") (class "Default")
      (node (ref "J15") (pin "2") (pinfunction "2_2") (pintype "bidirectional"))
      (node (ref "J17") (pin "B2") (pinfunction "B2_B2") (pintype "bidirectional"))
      (node (ref "J7") (pin "2") (pinfunction "2_2") (pintype "bidirectional"))
    )
    (net (code "21") (name "/DAC_OUT7_P") (class "Default")
      (node (ref "J15") (pin "1") (pinfunction "1_1") (pintype "bidirectional"))
      (node (ref "J17") (pin "B3") (pinfunction "B3_B3") (pintype "bidirectional"))
      (node (ref "J7") (pin "1") (pinfunction "1_1") (pintype "bidirectional"))
    )
    (net (code "22") (name "/DAC_OUT8_N") (class "Default")
      (node (ref "J16") (pin "2") (pinfunction "2_2") (pintype "bidirectional"))
      (node (ref "J17") (pin "A2") (pinfunction "A2_A2") (pintype "bidirectional"))
      (node (ref "J8") (pin "2") (pinfunction "2_2") (pintype "bidirectional"))
    )
    (net (code "23") (name "/DAC_OUT8_P") (class "Default")
      (node (ref "J16") (pin "1") (pinfunction "1_1") (pintype "bidirectional"))
      (node (ref "J17") (pin "A3") (pinfunction "A3_A3") (pintype "bidirectional"))
      (node (ref "J8") (pin "1") (pinfunction "1_1") (pintype "bidirectional"))
    )
    (net (code "24") (name "/LED1") (class "Default")
      (node (ref "IC1") (pin "4") (pinfunction "Q0_4") (pintype "output"))
      (node (ref "LD1") (pin "2") (pinfunction "A_2") (pintype "passive"))
    )
    (net (code "25") (name "/LED2") (class "Default")
      (node (ref "IC1") (pin "5") (pinfunction "Q1_5") (pintype "output"))
      (node (ref "LD2") (pin "2") (pinfunction "A_2") (pintype "passive"))
    )
    (net (code "26") (name "/LED3") (class "Default")
      (node (ref "IC1") (pin "6") (pinfunction "Q2_6") (pintype "output"))
      (node (ref "LD3") (pin "2") (pinfunction "A_2") (pintype "passive"))
    )
    (net (code "27") (name "/LED4") (class "Default")
      (node (ref "IC1") (pin "7") (pinfunction "Q3_7") (pintype "output"))
      (node (ref "LD4") (pin "2") (pinfunction "A_2") (pintype "passive"))
    )
    (net (code "28") (name "/LED5") (class "Default")
      (node (ref "IC1") (pin "14") (pinfunction "Q4_14") (pintype "output"))
      (node (ref "LD5") (pin "2") (pinfunction "A_2") (pintype "passive"))
    )
    (net (code "29") (name "/LED6") (class "Default")
      (node (ref "IC1") (pin "13") (pinfunction "Q5_13") (pintype "output"))
      (node (ref "LD6") (pin "2") (pinfunction "A_2") (pintype "passive"))
    )
    (net (code "30") (name "/LED7") (class "Default")
      (node (ref "IC1") (pin "12") (pinfunction "Q6_12") (pintype "output"))
      (node (ref "LD7") (pin "2") (pinfunction "A_2") (pintype "passive"))
    )
    (net (code "31") (name "/LED8") (class "Default")
      (node (ref "IC1") (pin "11") (pinfunction "Q7_11") (pintype "output"))
      (node (ref "LD8") (pin "2") (pinfunction "A_2") (pintype "passive"))
    )
    (net (code "32") (name "GND") (class "Default")
      (node (ref "C1") (pin "1") (pinfunction "1_1") (pintype "passive"))
      (node (ref "C2") (pin "1") (pinfunction "1_1") (pintype "passive"))
      (node (ref "C3") (pin "2") (pinfunction "2_2") (pintype "passive"))
      (node (ref "C4") (pin "2") (pinfunction "2_2") (pintype "passive"))
      (node (ref "C5") (pin "2") (pinfunction "2_2") (pintype "passive"))
      (node (ref "C6") (pin "2") (pinfunction "2_2") (pintype "passive"))
      (node (ref "IC1") (pin "8") (pinfunction "GND_8") (pintype "power_in"))
      (node (ref "J17") (pin "A1") (pinfunction "A1_A1") (pintype "bidirectional"))
      (node (ref "J17") (pin "A12") (pinfunction "A12_A12") (pintype "bidirectional"))
      (node (ref "J17") (pin "A15") (pinfunction "A15_A15") (pintype "bidirectional"))
      (node (ref "J17") (pin "A18") (pinfunction "A18_A18") (pintype "bidirectional"))
      (node (ref "J17") (pin "A4") (pinfunction "A4_A4") (pintype "bidirectional"))
      (node (ref "J17") (pin "A7") (pinfunction "A7_A7") (pintype "bidirectional"))
      (node (ref "J17") (pin "B1") (pinfunction "B1_B1") (pintype "bidirectional"))
      (node (ref "J17") (pin "B12") (pinfunction "B12_B12") (pintype "bidirectional"))
      (node (ref "J17") (pin "B15") (pinfunction "B15_B15") (pintype "bidirectional"))
      (node (ref "J17") (pin "B18") (pinfunction "B18_B18") (pintype "bidirectional"))
      (node (ref "J17") (pin "B4") (pinfunction "B4_B4") (pintype "bidirectional"))
      (node (ref "J17") (pin "B7") (pinfunction "B7_B7") (pintype "bidirectional"))
      (node (ref "J17") (pin "Shell1") (pinfunction "Shell1_Shell1") (pintype "bidirectional"))
      (node (ref "J17") (pin "Shell2") (pinfunction "Shell2_Shell2") (pintype "bidirectional"))
      (node (ref "J17") (pin "Shell3") (pinfunction "Shell3_Shell3") (pintype "bidirectional"))
      (node (ref "J17") (pin "Shell4") (pinfunction "Shell4_Shell4") (pintype "bidirectional"))
      (node (ref "J17") (pin "Shell5") (pinfunction "Shell5_Shell5") (pintype "bidirectional"))
      (node (ref "J17") (pin "Shell6") (pinfunction "Shell6_Shell6") (pintype "bidirectional"))
      (node (ref "R1") (pin "2") (pinfunction "2_2") (pintype "passive"))
      (node (ref "R10") (pin "2") (pinfunction "2_2") (pintype "passive"))
      (node (ref "R11") (pin "2") (pinfunction "2_2") (pintype "passive"))
      (node (ref "R12") (pin "2") (pinfunction "2_2") (pintype "passive"))
      (node (ref "R13") (pin "2") (pinfunction "2_2") (pintype "passive"))
      (node (ref "R14") (pin "2") (pinfunction "2_2") (pintype "passive"))
      (node (ref "R2") (pin "2") (pinfunction "2_2") (pintype "passive"))
      (node (ref "R3") (pin "2") (pinfunction "2_2") (pintype "passive"))
      (node (ref "R4") (pin "2") (pinfunction "2_2") (pintype "passive"))
      (node (ref "R5") (pin "2") (pinfunction "2_2") (pintype "passive"))
      (node (ref "R6") (pin "2") (pinfunction "2_2") (pintype "passive"))
      (node (ref "R7") (pin "2") (pinfunction "2_2") (pintype "passive"))
      (node (ref "R8") (pin "2") (pinfunction "2_2") (pintype "passive"))
      (node (ref "R9") (pin "2") (pinfunction "2_2") (pintype "passive"))
    )
    (net (code "33") (name "Net-(B1-Pad1)") (class "Default")
      (node (ref "B1") (pin "1") (pinfunction "1_1") (pintype "bidirectional"))
      (node (ref "C3") (pin "1") (pinfunction "1_1") (pintype "passive"))
      (node (ref "R3") (pin "1") (pinfunction "1_1") (pintype "passive"))
    )
    (net (code "34") (name "Net-(B2-Pad1)") (class "Default")
      (node (ref "B2") (pin "1") (pinfunction "1_1") (pintype "bidirectional"))
      (node (ref "C4") (pin "1") (pinfunction "1_1") (pintype "passive"))
      (node (ref "R4") (pin "1") (pinfunction "1_1") (pintype "passive"))
    )
    (net (code "35") (name "Net-(B3-Pad1)") (class "Default")
      (node (ref "B3") (pin "1") (pinfunction "1_1") (pintype "bidirectional"))
      (node (ref "C5") (pin "1") (pinfunction "1_1") (pintype "passive"))
      (node (ref "R13") (pin "1") (pinfunction "1_1") (pintype "passive"))
    )
    (net (code "36") (name "Net-(B4-Pad1)") (class "Default")
      (node (ref "B4") (pin "1") (pinfunction "1_1") (pintype "bidirectional"))
      (node (ref "C6") (pin "1") (pinfunction "1_1") (pintype "passive"))
      (node (ref "R14") (pin "1") (pinfunction "1_1") (pintype "passive"))
    )
    (net (code "37") (name "Net-(LD1-C)") (class "Default")
      (node (ref "LD1") (pin "1") (pinfunction "C_1") (pintype "passive"))
      (node (ref "R5") (pin "1") (pinfunction "1_1") (pintype "passive"))
    )
    (net (code "38") (name "Net-(LD2-C)") (class "Default")
      (node (ref "LD2") (pin "1") (pinfunction "C_1") (pintype "passive"))
      (node (ref "R6") (pin "1") (pinfunction "1_1") (pintype "passive"))
    )
    (net (code "39") (name "Net-(LD3-C)") (class "Default")
      (node (ref "LD3") (pin "1") (pinfunction "C_1") (pintype "passive"))
      (node (ref "R7") (pin "1") (pinfunction "1_1") (pintype "passive"))
    )
    (net (code "40") (name "Net-(LD4-C)") (class "Default")
      (node (ref "LD4") (pin "1") (pinfunction "C_1") (pintype "passive"))
      (node (ref "R8") (pin "1") (pinfunction "1_1") (pintype "passive"))
    )
    (net (code "41") (name "Net-(LD5-C)") (class "Default")
      (node (ref "LD5") (pin "1") (pinfunction "C_1") (pintype "passive"))
      (node (ref "R9") (pin "1") (pinfunction "1_1") (pintype "passive"))
    )
    (net (code "42") (name "Net-(LD6-C)") (class "Default")
      (node (ref "LD6") (pin "1") (pinfunction "C_1") (pintype "passive"))
      (node (ref "R10") (pin "1") (pinfunction "1_1") (pintype "passive"))
    )
    (net (code "43") (name "Net-(LD7-C)") (class "Default")
      (node (ref "LD7") (pin "1") (pinfunction "C_1") (pintype "passive"))
      (node (ref "R11") (pin "1") (pinfunction "1_1") (pintype "passive"))
    )
    (net (code "44") (name "Net-(LD8-C)") (class "Default")
      (node (ref "LD8") (pin "1") (pinfunction "C_1") (pintype "passive"))
      (node (ref "R12") (pin "1") (pinfunction "1_1") (pintype "passive"))
    )
    (net (code "45") (name "Net-(R1-Pad1)") (class "Default")
      (node (ref "R1") (pin "1") (pinfunction "1_1") (pintype "passive"))
      (node (ref "SW2") (pin "1") (pinfunction "1_1") (pintype "bidirectional"))
    )
    (net (code "46") (name "Net-(R2-Pad1)") (class "Default")
      (node (ref "R2") (pin "1") (pinfunction "1_1") (pintype "passive"))
      (node (ref "SW2") (pin "2") (pinfunction "2_2") (pintype "bidirectional"))
    )
    (net (code "47") (name "P3V3") (class "Default")
      (node (ref "C1") (pin "2") (pinfunction "2_2") (pintype "passive"))
      (node (ref "C2") (pin "2") (pinfunction "2_2") (pintype "passive"))
      (node (ref "IC1") (pin "16") (pinfunction "VCC_16") (pintype "power_in"))
      (node (ref "J17") (pin "A10") (pinfunction "A10_A10") (pintype "bidirectional"))
    )
    (net (code "48") (name "unconnected-(IC1-QS1-Pad9)") (class "Default")
      (node (ref "IC1") (pin "9") (pinfunction "QS1_9") (pintype "output"))
    )
    (net (code "49") (name "unconnected-(IC1-QS2-Pad10)") (class "Default")
      (node (ref "IC1") (pin "10") (pinfunction "QS2_10") (pintype "output"))
    )
    (net (code "50") (name "unconnected-(SW2-Pad3)") (class "Default")
      (node (ref "SW2") (pin "3") (pinfunction "3_3") (pintype "bidirectional"))
    )
    (net (code "51") (name "unconnected-(SW2-Pad4)") (class "Default")
      (node (ref "SW2") (pin "4") (pinfunction "4_4") (pintype "bidirectional"))
    )
    (net (code "52") (name "unconnected-(SW2-Pad5)") (class "Default")
      (node (ref "SW2") (pin "5") (pinfunction "5_5") (pintype "bidirectional"))
    )
    (net (code "53") (name "unconnected-(SW2-Pad6)") (class "Default")
      (node (ref "SW2") (pin "6") (pinfunction "6_6") (pintype "bidirectional"))
    )
    (net (code "54") (name "unconnected-(Standoff1-Pad1)") (class "Default")
      (node (ref "Standoff1") (pin "1") (pinfunction "1_1") (pintype "bidirectional"))
    )
    (net (code "55") (name "unconnected-(Standoff2-Pad1)") (class "Default")
      (node (ref "Standoff2") (pin "1") (pinfunction "1_1") (pintype "bidirectional"))
    )
    (net (code "56") (name "unconnected-(Standoff3-Pad1)") (class "Default")
      (node (ref "Standoff3") (pin "1") (pinfunction "1_1") (pintype "bidirectional"))
    )
    (net (code "57") (name "unconnected-(Standoff4-Pad1)") (class "Default")
      (node (ref "Standoff4") (pin "1") (pinfunction "1_1") (pintype "bidirectional"))
    )
  )
)
